# CouchProtato-PPG-MODULE.net
KiCad netlist of a schematic drawn in EAGLE
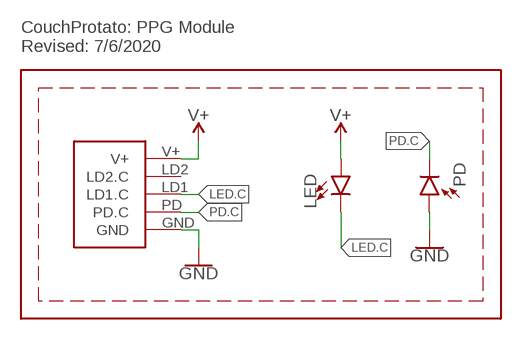
[diagram p0: schematic, sheet 1]

(export (version "E")
  (design (tool "Eeschema 10.0.6"))
  (components
    (comp (ref "LED")
      (value "LED0805")
      (footprint "eagle-import:LED-0805")
      (libsource (lib "eagle-import") (part "LED0805"))
    )
    (comp (ref "PD")
      (value "PHOTODIODE2-SMD.GULLWING")
      (footprint "eagle-import:2-SMD.GULLWING")
      (libsource (lib "eagle-import") (part "PHOTODIODE2-SMD.GULLWING"))
    )
    (comp (ref "U$3")
      (value "PPG.MODULE.2")
      (footprint "eagle-import:PPG.MODULE.2")
      (libsource (lib "eagle-import") (part "PPG.MODULE.2"))
    )
  )
  (nets
    (net (code "1") (name "GND") (class "Default")
      (node (ref "PD") (pin "+") (pinfunction "A_+") (pintype "passive"))
      (node (ref "U$3") (pin "GND") (pinfunction "GND_GND") (pintype "bidirectional"))
    )
    (net (code "2") (name "LED.C") (class "Default")
      (node (ref "LED") (pin "C") (pinfunction "C_C") (pintype "passive"))
      (node (ref "U$3") (pin "LD1") (pinfunction "LD1.C_LD1") (pintype "bidirectional"))
    )
    (net (code "3") (name "PD.C") (class "Default")
      (node (ref "PD") (pin "-") (pinfunction "C_-") (pintype "passive"))
      (node (ref "U$3") (pin "PD") (pinfunction "PD.C_PD") (pintype "bidirectional"))
    )
    (net (code "4") (name "V+") (class "Default")
      (node (ref "LED") (pin "A") (pinfunction "A_A") (pintype "passive"))
      (node (ref "U$3") (pin "V+") (pinfunction "V+_V+") (pintype "bidirectional"))
    )
    (net (code "5") (name "unconnected-(U$3-LD2.C-PadLD2)") (class "Default")
      (node (ref "U$3") (pin "LD2") (pinfunction "LD2.C_LD2") (pintype "bidirectional"))
    )
  )
)
